# Power_Management.net
KiCad netlist of a schematic drawn in Altium Designer
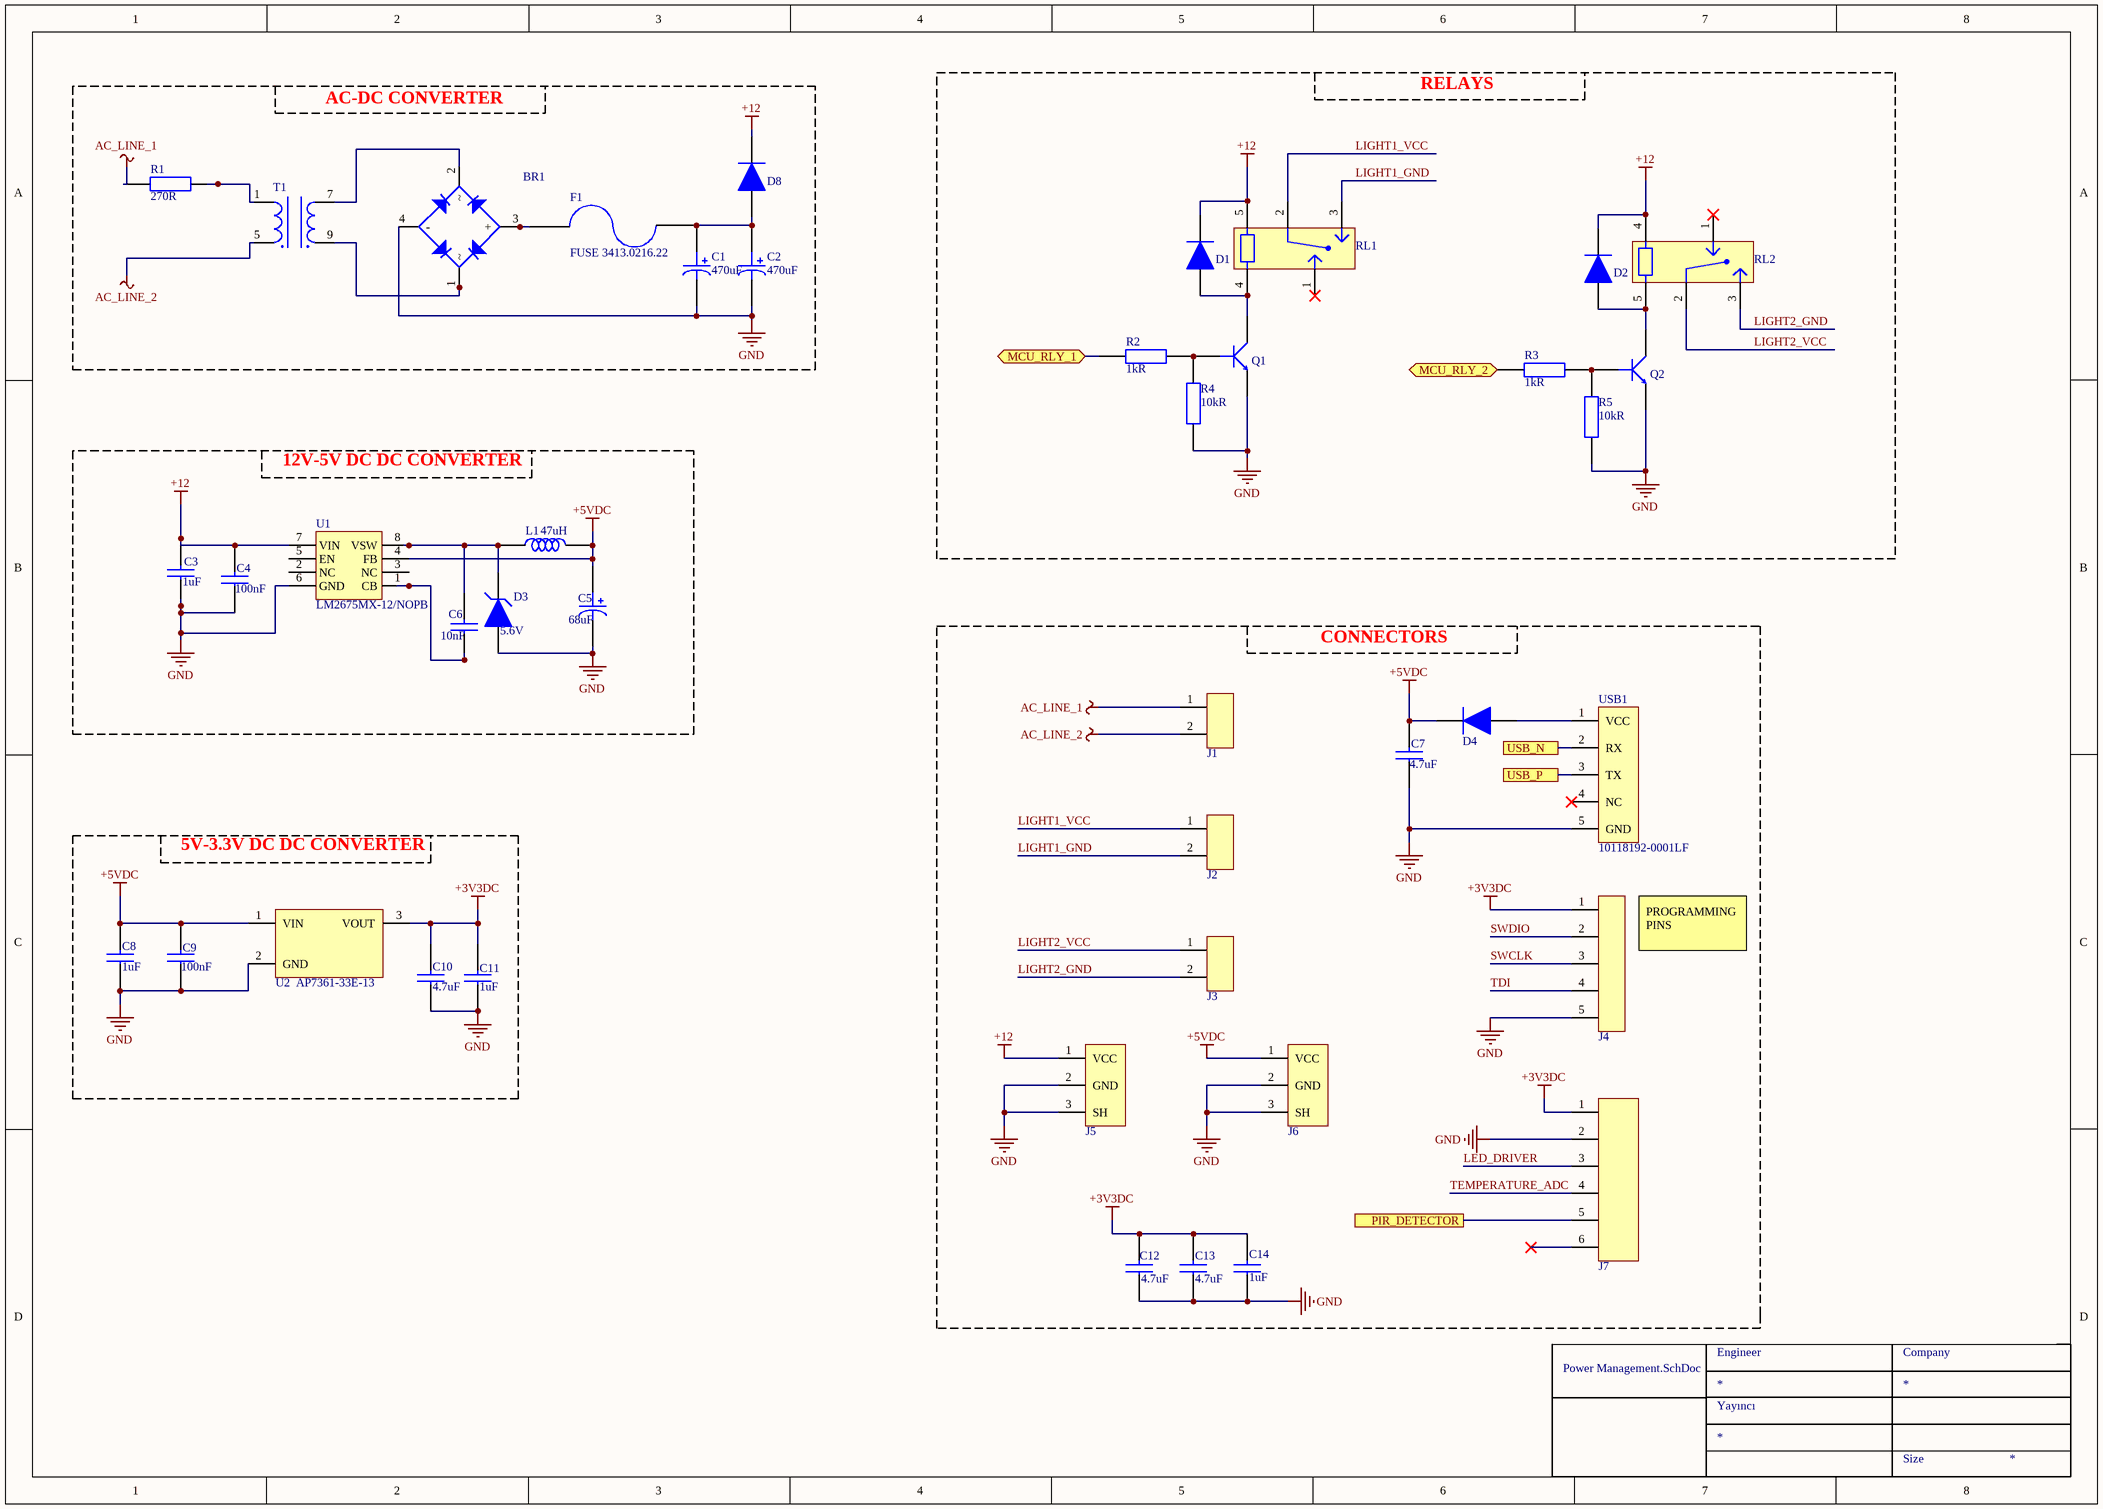
[diagram p0: Power Management.SchDoc]

(export (version "E")
  (design (tool "Eeschema 10.0.6"))
  (components
    (comp (ref "BR1")
      (value "~")
      (footprint "DB105STR")
      (description "Bridge Rect 1PHASE 600V 1A Db-s")
      (fields
        (field (name "MANUFACTURER") "Sangdest Microelectronics")
        (field (name "MANUFACTURER PART NUMBER") "DB105STR")
      )
      (libsource (lib "Uproject") (part "DB105STR"))
    )
    (comp (ref "C1")
      (value "470uF")
      (footprint "CAP_RADIAL_D10_P5")
      (description "CAP ALU ELEC 470uF 50V RADIAL")
      (libsource (lib "Uproject") (part "ESH477M050AH4AA"))
    )
    (comp (ref "C2")
      (value "470uF")
      (footprint "CAP_RADIAL_D10_P5")
      (description "CAP ALU ELEC 470uF 50V RADIAL")
      (libsource (lib "Uproject") (part "ESH477M050AH4AA"))
    )
    (comp (ref "C3")
      (value "CL21B105KBFNNNE")
      (footprint "CAP_0805")
      (description "CAP CER 1uF %10 0805")
      (fields
        (field (name "MANUFACTURER") "Samsung")
        (field (name "TOLERANCE") "10%")
        (field (name "CAPACITANCE") "1uF")
        (field (name "DESIGNED BY") "BERK")
      )
      (libsource (lib "UDEMY_Library") (part "CAP CER 1uF 0805"))
    )
    (comp (ref "C4")
      (value "C0603C104K5RACTU")
      (footprint "CAP_0603")
      (description "CAP CER 100nF %10 0603 SMD")
      (fields
        (field (name "MANUFACTURER") "KEMET")
        (field (name "TOLERANCE") "10%")
        (field (name "CAPACITANCE") "100nF")
        (field (name "DESIGNED BY") "BERK")
      )
      (libsource (lib "UDEMY_Library") (part "CAP CER 100nF 0603"))
    )
    (comp (ref "C5")
      (value "EEV686M035A9HAA")
      (footprint "CAP_EEVseries")
      (description "Cap Aluminum Lytic 68uF 35V 20% (6.3 X 7.7mm) SMD 280mA 2000h 105C T/R")
      (fields
        (field (name "MANUFACTURER") "KEMET")
        (field (name "TOLERANCE") "20%")
        (field (name "CAPACITANCE") "68uF")
      )
      (libsource (lib "UDEMY_Library") (part "CAP ALU 68uF"))
    )
    (comp (ref "C6")
      (value "0603B103K160CT")
      (footprint "CAP_0603")
      (description "CAP CER 10nF %10 0603")
      (fields
        (field (name "MANUFACTURER") "Walsin Technologies")
        (field (name "TOLERANCE") "10%")
        (field (name "CAPACITANCE") "10nF")
        (field (name "DESIGNED BY") "BERK")
      )
      (libsource (lib "UDEMY_Library") (part "CAP CER 10nF 0603"))
    )
    (comp (ref "C7")
      (value "CL21A475KAQNNNE")
      (footprint "CAP_0805")
      (description "CAP CER 4.7uF %10 0805")
      (fields
        (field (name "MANUFACTURER") "Samsung")
        (field (name "TOLERANCE") "10%")
        (field (name "CAPACITANCE") "4.7uF")
        (field (name "DESIGNED BY") "BERK")
      )
      (libsource (lib "UDEMY_Library") (part "CAP CER 4.7uF 0805"))
    )
    (comp (ref "C8")
      (value "CL21B105KBFNNNE")
      (footprint "CAP_0805")
      (description "CAP CER 1uF %10 0805")
      (fields
        (field (name "MANUFACTURER") "Samsung")
        (field (name "TOLERANCE") "10%")
        (field (name "CAPACITANCE") "1uF")
        (field (name "DESIGNED BY") "BERK")
      )
      (libsource (lib "UDEMY_Library") (part "CAP CER 1uF 0805"))
    )
    (comp (ref "C9")
      (value "C0603C104K5RACTU")
      (footprint "CAP_0603")
      (description "CAP CER 100nF %10 0603 SMD")
      (fields
        (field (name "MANUFACTURER") "KEMET")
        (field (name "TOLERANCE") "10%")
        (field (name "CAPACITANCE") "100nF")
        (field (name "DESIGNED BY") "BERK")
      )
      (libsource (lib "UDEMY_Library") (part "CAP CER 100nF 0603"))
    )
    (comp (ref "C10")
      (value "CL21A475KAQNNNE")
      (footprint "CAP_0805")
      (description "CAP CER 4.7uF %10 0805")
      (fields
        (field (name "MANUFACTURER") "Samsung")
        (field (name "TOLERANCE") "10%")
        (field (name "CAPACITANCE") "4.7uF")
        (field (name "DESIGNED BY") "BERK")
      )
      (libsource (lib "UDEMY_Library") (part "CAP CER 4.7uF 0805"))
    )
    (comp (ref "C11")
      (value "CL21B105KBFNNNE")
      (footprint "CAP_0805")
      (description "CAP CER 1uF %10 0805")
      (fields
        (field (name "MANUFACTURER") "Samsung")
        (field (name "TOLERANCE") "10%")
        (field (name "CAPACITANCE") "1uF")
        (field (name "DESIGNED BY") "BERK")
      )
      (libsource (lib "UDEMY_Library") (part "CAP CER 1uF 0805"))
    )
    (comp (ref "C12")
      (value "CL21A475KAQNNNE")
      (footprint "CAP_0805")
      (description "CAP CER 4.7uF %10 0805")
      (fields
        (field (name "MANUFACTURER") "Samsung")
        (field (name "TOLERANCE") "10%")
        (field (name "CAPACITANCE") "4.7uF")
        (field (name "DESIGNED BY") "BERK")
      )
      (libsource (lib "UDEMY_Library") (part "CAP CER 4.7uF 0805"))
    )
    (comp (ref "C13")
      (value "CL21A475KAQNNNE")
      (footprint "CAP_0805")
      (description "CAP CER 4.7uF %10 0805")
      (fields
        (field (name "MANUFACTURER") "Samsung")
        (field (name "TOLERANCE") "10%")
        (field (name "CAPACITANCE") "4.7uF")
        (field (name "DESIGNED BY") "BERK")
      )
      (libsource (lib "UDEMY_Library") (part "CAP CER 4.7uF 0805"))
    )
    (comp (ref "C14")
      (value "CL21B105KBFNNNE")
      (footprint "CAP_0805")
      (description "CAP CER 1uF %10 0805")
      (fields
        (field (name "MANUFACTURER") "Samsung")
        (field (name "TOLERANCE") "10%")
        (field (name "CAPACITANCE") "1uF")
        (field (name "DESIGNED BY") "BERK")
      )
      (libsource (lib "UDEMY_Library") (part "CAP CER 1uF 0805"))
    )
    (comp (ref "D1")
      (value "1N4148WS")
      (footprint "SOD323F")
      (description "Diode, Single, 75 V, 150 mA, 1 V, 4 ns")
      (fields
        (field (name "MANUFACTURER") "ON Semiconductor / Fairchild")
        (field (name "DESIGNED BY") "BERK")
      )
      (libsource (lib "UDEMY_Library") (part "1N4148WS"))
    )
    (comp (ref "D2")
      (value "1N4148WS")
      (footprint "SOD323F")
      (description "Diode, Single, 75 V, 150 mA, 1 V, 4 ns")
      (fields
        (field (name "MANUFACTURER") "ON Semiconductor / Fairchild")
        (field (name "DESIGNED BY") "BERK")
      )
      (libsource (lib "UDEMY_Library") (part "1N4148WS"))
    )
    (comp (ref "D3")
      (value "1SMB5919BT3G")
      (footprint "SMB")
      (description "Diode Zener Single 5.6V 5% 3W 2-Pin SMB T/R")
      (fields
        (field (name "MANUFACTURER") "ON Semiconductor")
        (field (name "TOLERANCE") "5%")
        (field (name "WORKING VOLTAGE") "5.6V")
        (field (name "DESIGNED BY") "BERK")
      )
      (libsource (lib "UDEMY_Library") (part "1SMB5919BT3G"))
    )
    (comp (ref "D4")
      (value "1N4148WS")
      (footprint "SOD323F")
      (description "Diode, Single, 75 V, 150 mA, 1 V, 4 ns")
      (fields
        (field (name "MANUFACTURER") "ON Semiconductor / Fairchild")
        (field (name "DESIGNED BY") "BERK")
      )
      (libsource (lib "UDEMY_Library") (part "1N4148WS"))
    )
    (comp (ref "D8")
      (value "1N4148WS")
      (footprint "SOD323F")
      (description "Diode, Single, 75 V, 150 mA, 1 V, 4 ns")
      (fields
        (field (name "MANUFACTURER") "ON Semiconductor / Fairchild")
        (field (name "DESIGNED BY") "BERK")
      )
      (libsource (lib "UDEMY_Library") (part "1N4148WS"))
    )
    (comp (ref "F1")
      (value "FUSE 3413.0216.22")
      (footprint "3413.0216.22")
      (description "Fuse Chip Fast Acting 1A 32V SMD Solder Pad 1206 Glass T/R VDE/cULus")
      (fields
        (field (name "MANUFACTURER") "Schurter")
        (field (name "MANUFACTURER PART NUMBER") "3413.0216.22")
      )
      (libsource (lib "Uproject") (part "FUSE 3413.0216.22"))
    )
    (comp (ref "J1")
      (value "TBP01R1-508-02BE")
      (footprint "TBP01R1-508")
      (description "Conn Shrouded Header HDR 2 POS 5.08mm Solder RA Side Entry Thru-Hole Bag")
      (fields (field (name "MANUFACTURER") "CUI") (field (name "DESIGNED BY") "BERK"))
      (libsource (lib "UDEMY_Library") (part "TBP01R1-508-02BE"))
    )
    (comp (ref "J2")
      (value "TBP01R1-508-02BE")
      (footprint "TBP01R1-508")
      (description "Conn Shrouded Header HDR 2 POS 5.08mm Solder RA Side Entry Thru-Hole Bag")
      (fields (field (name "MANUFACTURER") "CUI") (field (name "DESIGNED BY") "BERK"))
      (libsource (lib "UDEMY_Library") (part "TBP01R1-508-02BE"))
    )
    (comp (ref "J3")
      (value "TBP01R1-508-02BE")
      (footprint "TBP01R1-508")
      (description "Conn Shrouded Header HDR 2 POS 5.08mm Solder RA Side Entry Thru-Hole Bag")
      (fields (field (name "MANUFACTURER") "CUI") (field (name "DESIGNED BY") "BERK"))
      (libsource (lib "UDEMY_Library") (part "TBP01R1-508-02BE"))
    )
    (comp (ref "J4")
      (value "SMH-105-02-L-S")
      (footprint "PINHEADER1X5_RA")
      (description ".100 C.L. HORIZONTAL SMT SOCKET")
      (fields (field (name "MANUFACTURER") "Samtec") (field (name "DESIGNED BY") "BERK"))
      (libsource (lib "UDEMY_Library") (part "SMH-105-02-L-S"))
    )
    (comp (ref "J5")
      (value "PJ-037AH-SMT-TR")
      (footprint "JACK")
      (description "DC Power Connectors Power Jacks")
      (fields (field (name "MANUFACTURER") "CUI") (field (name "DESIGNED BY") "BERK"))
      (libsource (lib "UDEMY_Library") (part "PJ-037AH-SMT-TR"))
    )
    (comp (ref "J6")
      (value "PJ-037AH-SMT-TR")
      (footprint "JACK")
      (description "DC Power Connectors Power Jacks")
      (fields (field (name "MANUFACTURER") "CUI") (field (name "DESIGNED BY") "BERK"))
      (libsource (lib "UDEMY_Library") (part "PJ-037AH-SMT-TR"))
    )
    (comp (ref "J7")
      (value "64800611622")
      (footprint "64800611622")
      (description "1.50mm 6PIN Connector")
      (fields (field (name "MANUFACTURER") "Wurth Electronics"))
      (libsource (lib "UDEMY_Library") (part "64800611622_conn_6pin"))
    )
    (comp (ref "L1")
      (value "78438335470")
      (footprint "IND_1212")
      (description "FIXED IND 47UH 390MA 2.3 OHM SMD")
      (fields
        (field (name "MANUFACTURER") "Wurth Electronics")
        (field (name "TOLERANCE") "30%")
        (field (name "INDUCTANCE") "47uH")
        (field (name "DESIGNED BY") "BERK")
      )
      (libsource (lib "UDEMY_Library") (part "IND 47uH"))
    )
    (comp (ref "Q1")
      (value "MMBT3904-7-F")
      (footprint "SOT-23F")
      (description "Transistor General Purpose BJT NPN 40 Volt 0.2A Automotive 3-Pin SOT-23")
      (fields (field (name "MANUFACTURER") "Diodes Zetex") (field (name "DESIGNED BY") "BERK"))
      (libsource (lib "UDEMY_Library") (part "MMBT3904-7-F"))
    )
    (comp (ref "Q2")
      (value "MMBT3904-7-F")
      (footprint "SOT-23F")
      (description "Transistor General Purpose BJT NPN 40 Volt 0.2A Automotive 3-Pin SOT-23")
      (fields (field (name "MANUFACTURER") "Diodes Zetex") (field (name "DESIGNED BY") "BERK"))
      (libsource (lib "UDEMY_Library") (part "MMBT3904-7-F"))
    )
    (comp (ref "R1")
      (value "5WD27")
      (footprint "RES_AXIAL_W")
      (description "Resistor 5 Watt Cermet Wirewound Flameproof .27 Ohm 5% Axial Lead")
      (fields
        (field (name "MANUFACTURER") "NTE Electronics")
        (field (name "TOLERANCE") "5%")
        (field (name "RESISTANCE") "270R")
      )
      (libsource (lib "Uproject") (part "5WD27"))
    )
    (comp (ref "R2")
      (value "RC0603FR-0710KL")
      (footprint "RES_0603")
      (description "RES 1K %1 OHM 0603 SMD")
      (fields
        (field (name "MANUFACTURER") "Yageo")
        (field (name "MANUFACTURER PART NUMBER") "RC0603JR-071KL")
        (field (name "RESISTANCE") "1kR")
        (field (name "DESIGNED BY") "BERK")
      )
      (libsource (lib "UDEMY_Library") (part "RES 1K OHM 0603"))
    )
    (comp (ref "R3")
      (value "RC0603FR-0710KL")
      (footprint "RES_0603")
      (description "RES 1K %1 OHM 0603 SMD")
      (fields
        (field (name "MANUFACTURER") "Yageo")
        (field (name "MANUFACTURER PART NUMBER") "RC0603JR-071KL")
        (field (name "RESISTANCE") "1kR")
        (field (name "DESIGNED BY") "BERK")
      )
      (libsource (lib "UDEMY_Library") (part "RES 1K OHM 0603"))
    )
    (comp (ref "R4")
      (value "RC0603FR-0710KL")
      (footprint "RES_0603")
      (description "RES 10K %1 OHM 0603 SMD")
      (fields
        (field (name "MANUFACTURER") "Yageo")
        (field (name "TOLERANCE") "1%")
        (field (name "RESISTANCE") "10kR")
        (field (name "DESIGNED BY") "BERK")
      )
      (libsource (lib "UDEMY_Library") (part "RES 10K OHM 0603"))
    )
    (comp (ref "R5")
      (value "RC0603FR-0710KL")
      (footprint "RES_0603")
      (description "RES 10K %1 OHM 0603 SMD")
      (fields
        (field (name "MANUFACTURER") "Yageo")
        (field (name "TOLERANCE") "1%")
        (field (name "RESISTANCE") "10kR")
        (field (name "DESIGNED BY") "BERK")
      )
      (libsource (lib "UDEMY_Library") (part "RES 10K OHM 0603"))
    )
    (comp (ref "RL1")
      (value "ALQ112")
      (footprint "ALQ112")
      (description "General Purpose Relay SPDT (1 Form C) 12VDC Coil Through Hole")
      (fields (field (name "MANUFACTURER") "Panasonic") (field (name "DESIGNED BY") "BERK"))
      (libsource (lib "") (part "ALQ112_1"))
    )
    (comp (ref "RL2")
      (value "ALQ112")
      (footprint "ALQ112")
      (description "General Purpose Relay SPDT (1 Form C) 12VDC Coil Through Hole")
      (fields (field (name "MANUFACTURER") "Panasonic") (field (name "DESIGNED BY") "BERK"))
      (libsource (lib "UDEMY_Library") (part "ALQ112"))
    )
    (comp (ref "T1")
      (value "BV302S12010-ZU")
      (footprint "BV302S")
      (description "Pwr Xfmr Laminated 1VA Th")
      (fields (field (name "MANUFACTURER") "Zettler Magnetics"))
      (libsource (lib "Uproject") (part "BV302S12010-ZU"))
    )
    (comp (ref "U1")
      (value "LM2675MX-12/NOPB")
      (footprint "SOIC8")
      (description "SIMPLE SWITCHER® 6.5V to 40V, 1A Low Component Count Step-Down Regulator 8-SOIC -40 to 125")
      (fields (field (name "MANUFACTURER") "TI National Semiconductor"))
      (libsource (lib "Uproject") (part "LM2675MX-12/NOPB"))
    )
    (comp (ref "U2")
      (value "AP7361-33E-13")
      (footprint "SOT223")
      (description "LDO Regulator Pos 3.3V 1A 4-Pin(3+Tab) SOT-223 T/R")
      (fields (field (name "MANUFACTURER") "Diodes") (field (name "DESIGNED BY") "BERK"))
      (libsource (lib "UDEMY_Library") (part "AP7361-33E-13"))
    )
    (comp (ref "USB1")
      (value "10118192-0001LF")
      (footprint "MICRO_B_USB")
      (description "CONN RCPT USB2.0 MICRO B SMD R/A")
      (fields (field (name "MANUFACTURER") "Amphenol FCI") (field (name "DESIGNED BY") "BERK"))
      (libsource (lib "UDEMY_Library") (part "Micro B USB Connector"))
    )
  )
  (nets
    (net (code "1") (name "+3V3DC") (class "Default")
      (node (ref "C10") (pin "2") (pinfunction "2_2") (pintype "passive"))
      (node (ref "C11") (pin "2") (pinfunction "2_2") (pintype "passive"))
      (node (ref "C12") (pin "2") (pinfunction "2_2") (pintype "passive"))
      (node (ref "C13") (pin "2") (pinfunction "2_2") (pintype "passive"))
      (node (ref "C14") (pin "2") (pinfunction "2_2") (pintype "passive"))
      (node (ref "J4") (pin "1") (pinfunction "1_1") (pintype "power_in"))
      (node (ref "J7") (pin "1") (pintype "power_in"))
      (node (ref "U2") (pin "3") (pinfunction "VOUT_3") (pintype "passive"))
    )
    (net (code "2") (name "+5VDC") (class "Default")
      (node (ref "C5") (pin "1") (pinfunction "1_1") (pintype "passive"))
      (node (ref "C7") (pin "2") (pinfunction "2_2") (pintype "passive"))
      (node (ref "C8") (pin "2") (pinfunction "2_2") (pintype "passive"))
      (node (ref "C9") (pin "2") (pinfunction "2_2") (pintype "passive"))
      (node (ref "D4") (pin "1") (pinfunction "1_1") (pintype "power_in"))
      (node (ref "J6") (pin "1") (pinfunction "VCC_1") (pintype "power_in"))
      (node (ref "L1") (pin "2") (pinfunction "2_2") (pintype "passive"))
      (node (ref "U1") (pin "4") (pinfunction "FB_4") (pintype "passive"))
      (node (ref "U2") (pin "1") (pinfunction "VIN_1") (pintype "passive"))
    )
    (net (code "3") (name "+12") (class "Default")
      (node (ref "C3") (pin "2") (pinfunction "2_2") (pintype "passive"))
      (node (ref "C4") (pin "2") (pinfunction "2_2") (pintype "passive"))
      (node (ref "D1") (pin "1") (pinfunction "1_1") (pintype "power_in"))
      (node (ref "D2") (pin "1") (pinfunction "1_1") (pintype "power_in"))
      (node (ref "D8") (pin "1") (pinfunction "1_1") (pintype "power_in"))
      (node (ref "J5") (pin "1") (pinfunction "VCC_1") (pintype "power_in"))
      (node (ref "RL1") (pin "5") (pinfunction "5_5") (pintype "passive"))
      (node (ref "RL2") (pin "4") (pinfunction "4_4") (pintype "passive"))
      (node (ref "U1") (pin "7") (pinfunction "VIN_7") (pintype "passive"))
    )
    (net (code "4") (name "/LED_DRIVER") (class "Default") (node (ref "J7") (pin "3") (pintype "power_in")))
    (net (code "5") (name "/LIGHT1_GND") (class "Default")
      (node (ref "J2") (pin "2") (pinfunction "2_2") (pintype "power_in"))
      (node (ref "RL1") (pin "3") (pinfunction "3_3") (pintype "passive"))
    )
    (net (code "6") (name "/LIGHT1_VCC") (class "Default")
      (node (ref "J2") (pin "1") (pinfunction "1_1") (pintype "power_in"))
      (node (ref "RL1") (pin "2") (pinfunction "2_2") (pintype "passive"))
    )
    (net (code "7") (name "/LIGHT2_GND") (class "Default")
      (node (ref "J3") (pin "2") (pinfunction "2_2") (pintype "power_in"))
      (node (ref "RL2") (pin "3") (pinfunction "3_3") (pintype "passive"))
    )
    (net (code "8") (name "/LIGHT2_VCC") (class "Default")
      (node (ref "J3") (pin "1") (pinfunction "1_1") (pintype "power_in"))
      (node (ref "RL2") (pin "2") (pinfunction "2_2") (pintype "passive"))
    )
    (net (code "9") (name "/MCU_RLY_1") (class "Default")
      (node (ref "R2") (pin "1") (pinfunction "1_1") (pintype "passive"))
    )
    (net (code "10") (name "/MCU_RLY_2") (class "Default")
      (node (ref "R3") (pin "1") (pinfunction "1_1") (pintype "passive"))
    )
    (net (code "11") (name "/PIR_DETECTOR") (class "Default")
      (node (ref "J7") (pin "5") (pintype "power_in"))
    )
    (net (code "12") (name "/SWCLK") (class "Default")
      (node (ref "J4") (pin "3") (pinfunction "3_3") (pintype "power_in"))
    )
    (net (code "13") (name "/SWDIO") (class "Default")
      (node (ref "J4") (pin "2") (pinfunction "2_2") (pintype "power_in"))
    )
    (net (code "14") (name "/TDI") (class "Default")
      (node (ref "J4") (pin "4") (pinfunction "4_4") (pintype "power_in"))
    )
    (net (code "15") (name "/TEMPERATURE_ADC") (class "Default")
      (node (ref "J7") (pin "4") (pintype "power_in"))
    )
    (net (code "16") (name "/USB_N") (class "Default")
      (node (ref "USB1") (pin "2") (pinfunction "RX_2") (pintype "power_in"))
    )
    (net (code "17") (name "/USB_P") (class "Default")
      (node (ref "USB1") (pin "3") (pinfunction "TX_3") (pintype "power_in"))
    )
    (net (code "18") (name "AC_LINE_1") (class "Default")
      (node (ref "J1") (pin "1") (pinfunction "1_1") (pintype "power_in"))
      (node (ref "R1") (pin "1") (pinfunction "1_1") (pintype "passive"))
    )
    (net (code "19") (name "AC_LINE_2") (class "Default")
      (node (ref "J1") (pin "2") (pinfunction "2_2") (pintype "power_in"))
      (node (ref "T1") (pin "5") (pintype "passive"))
    )
    (net (code "20") (name "GND") (class "Default")
      (node (ref "BR1") (pin "4") (pinfunction "-_4") (pintype "passive"))
      (node (ref "C1") (pin "2") (pinfunction "2_2") (pintype "passive"))
      (node (ref "C10") (pin "1") (pinfunction "1_1") (pintype "passive"))
      (node (ref "C11") (pin "1") (pinfunction "1_1") (pintype "passive"))
      (node (ref "C12") (pin "1") (pinfunction "1_1") (pintype "passive"))
      (node (ref "C13") (pin "1") (pinfunction "1_1") (pintype "passive"))
      (node (ref "C14") (pin "1") (pinfunction "1_1") (pintype "passive"))
      (node (ref "C2") (pin "2") (pinfunction "2_2") (pintype "passive"))
      (node (ref "C3") (pin "1") (pinfunction "1_1") (pintype "passive"))
      (node (ref "C4") (pin "1") (pinfunction "1_1") (pintype "passive"))
      (node (ref "C5") (pin "2") (pinfunction "2_2") (pintype "passive"))
      (node (ref "C7") (pin "1") (pinfunction "1_1") (pintype "passive"))
      (node (ref "C8") (pin "1") (pinfunction "1_1") (pintype "passive"))
      (node (ref "C9") (pin "1") (pinfunction "1_1") (pintype "passive"))
      (node (ref "D3") (pin "A") (pinfunction "A_A") (pintype "passive"))
      (node (ref "J4") (pin "5") (pinfunction "5_5") (pintype "power_in"))
      (node (ref "J5") (pin "2") (pinfunction "GND_2") (pintype "power_in"))
      (node (ref "J5") (pin "3") (pinfunction "SH_3") (pintype "power_in"))
      (node (ref "J6") (pin "2") (pinfunction "GND_2") (pintype "power_in"))
      (node (ref "J6") (pin "3") (pinfunction "SH_3") (pintype "power_in"))
      (node (ref "J7") (pin "2") (pintype "power_in"))
      (node (ref "Q1") (pin "2") (pinfunction "E_2") (pintype "power_in"))
      (node (ref "Q2") (pin "2") (pinfunction "E_2") (pintype "power_in"))
      (node (ref "R4") (pin "1") (pinfunction "1_1") (pintype "passive"))
      (node (ref "R5") (pin "1") (pinfunction "1_1") (pintype "passive"))
      (node (ref "U1") (pin "6") (pinfunction "GND_6") (pintype "passive"))
      (node (ref "U2") (pin "2") (pinfunction "GND_2") (pintype "passive"))
      (node (ref "USB1") (pin "5") (pinfunction "GND_5") (pintype "power_in"))
    )
    (net (code "21") (name "Net-(BR1-+)") (class "Default")
      (node (ref "BR1") (pin "3") (pinfunction "+_3") (pintype "passive"))
      (node (ref "F1") (pin "1") (pintype "passive"))
    )
    (net (code "22") (name "Net-(BR1-~-Pad1)") (class "Default")
      (node (ref "BR1") (pin "1") (pinfunction "~_1") (pintype "passive"))
      (node (ref "T1") (pin "9") (pintype "passive"))
    )
    (net (code "23") (name "Net-(BR1-~-Pad2)") (class "Default")
      (node (ref "BR1") (pin "2") (pinfunction "~_2") (pintype "passive"))
      (node (ref "T1") (pin "7") (pintype "passive"))
    )
    (net (code "24") (name "Net-(C1-Pad1)") (class "Default")
      (node (ref "C1") (pin "1") (pinfunction "1_1") (pintype "passive"))
      (node (ref "C2") (pin "1") (pinfunction "1_1") (pintype "passive"))
      (node (ref "D8") (pin "2") (pinfunction "2_2") (pintype "power_in"))
      (node (ref "F1") (pin "2") (pintype "passive"))
    )
    (net (code "25") (name "Net-(Q1-B)") (class "Default")
      (node (ref "Q1") (pin "1") (pinfunction "B_1") (pintype "power_in"))
      (node (ref "R2") (pin "2") (pinfunction "2_2") (pintype "passive"))
      (node (ref "R4") (pin "2") (pinfunction "2_2") (pintype "passive"))
    )
    (net (code "26") (name "Net-(Q1-C)") (class "Default")
      (node (ref "D1") (pin "2") (pinfunction "2_2") (pintype "power_in"))
      (node (ref "Q1") (pin "3") (pinfunction "C_3") (pintype "power_in"))
      (node (ref "RL1") (pin "4") (pinfunction "4_4") (pintype "passive"))
    )
    (net (code "27") (name "Net-(Q2-B)") (class "Default")
      (node (ref "Q2") (pin "1") (pinfunction "B_1") (pintype "power_in"))
      (node (ref "R3") (pin "2") (pinfunction "2_2") (pintype "passive"))
      (node (ref "R5") (pin "2") (pinfunction "2_2") (pintype "passive"))
    )
    (net (code "28") (name "Net-(Q2-C)") (class "Default")
      (node (ref "D2") (pin "2") (pinfunction "2_2") (pintype "power_in"))
      (node (ref "Q2") (pin "3") (pinfunction "C_3") (pintype "power_in"))
      (node (ref "RL2") (pin "5") (pinfunction "5_5") (pintype "passive"))
    )
    (net (code "29") (name "Net-(R1-Pad2)") (class "Default")
      (node (ref "R1") (pin "2") (pinfunction "2_2") (pintype "passive"))
      (node (ref "T1") (pin "1") (pintype "passive"))
    )
    (net (code "30") (name "Net-(U1-CB)") (class "Default")
      (node (ref "C6") (pin "1") (pinfunction "1_1") (pintype "passive"))
      (node (ref "U1") (pin "1") (pinfunction "CB_1") (pintype "passive"))
    )
    (net (code "31") (name "Net-(U1-VSW)") (class "Default")
      (node (ref "C6") (pin "2") (pinfunction "2_2") (pintype "passive"))
      (node (ref "D3") (pin "C") (pinfunction "C_C") (pintype "passive"))
      (node (ref "L1") (pin "1") (pinfunction "1_1") (pintype "passive"))
      (node (ref "U1") (pin "8") (pinfunction "VSW_8") (pintype "passive"))
    )
    (net (code "32") (name "Net-(USB1-VCC)") (class "Default")
      (node (ref "D4") (pin "2") (pinfunction "2_2") (pintype "power_in"))
      (node (ref "USB1") (pin "1") (pinfunction "VCC_1") (pintype "power_in"))
    )
    (net (code "33") (name "unconnected-(J7-Pad6)") (class "Default")
      (node (ref "J7") (pin "6") (pintype "power_in+no_connect"))
    )
    (net (code "34") (name "unconnected-(RL1-Pad1)") (class "Default")
      (node (ref "RL1") (pin "1") (pinfunction "1_1") (pintype "passive+no_connect"))
    )
    (net (code "35") (name "unconnected-(RL2-Pad1)") (class "Default")
      (node (ref "RL2") (pin "1") (pinfunction "1_1") (pintype "passive+no_connect"))
    )
    (net (code "36") (name "unconnected-(U1-EN-Pad5)") (class "Default")
      (node (ref "U1") (pin "5") (pinfunction "EN_5") (pintype "passive"))
    )
    (net (code "37") (name "unconnected-(U1-NC-Pad2)") (class "Default")
      (node (ref "U1") (pin "2") (pinfunction "NC_2") (pintype "passive"))
    )
    (net (code "38") (name "unconnected-(U1-NC-Pad3)") (class "Default")
      (node (ref "U1") (pin "3") (pinfunction "NC_3") (pintype "passive"))
    )
    (net (code "39") (name "unconnected-(USB1-NC-Pad4)") (class "Default")
      (node (ref "USB1") (pin "4") (pinfunction "NC_4") (pintype "power_in+no_connect"))
    )
  )
)
